# AMFS_PCB5.net
KiCad netlist of a schematic drawn in EAGLE
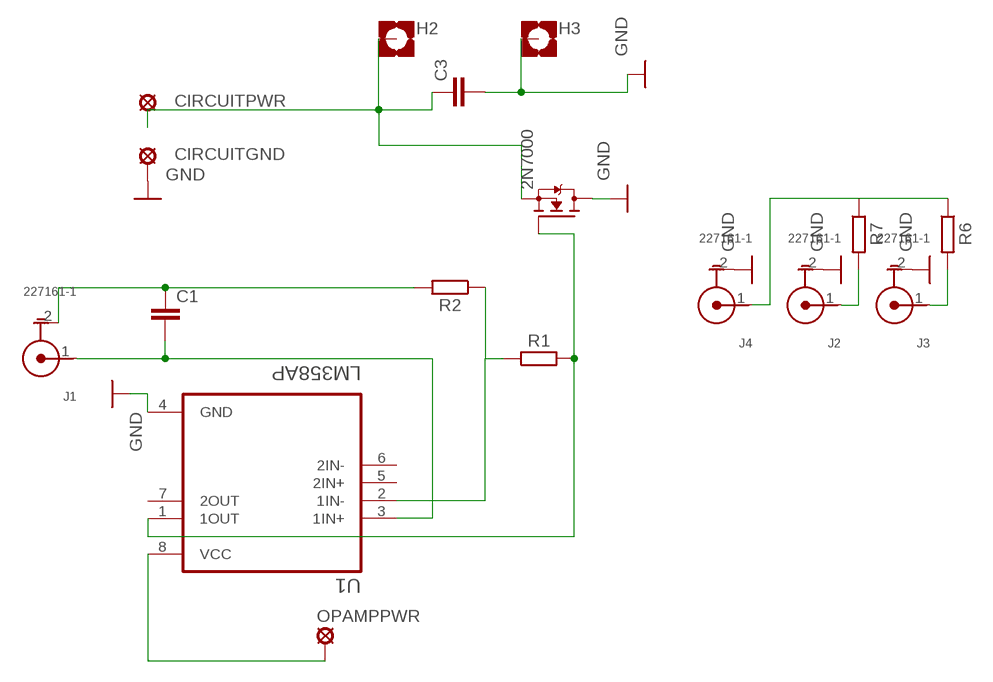
[diagram p0: schematic, sheet 1]

(export (version "E")
  (design (tool "Eeschema 10.0.6"))
  (components
    (comp (ref "C1")
      (value "C5/3.5")
      (footprint "eagle-import:C5B3.5")
      (libsource (lib "eagle-import") (part "C5/3.5"))
    )
    (comp (ref "C3")
      (value "C5/3.5")
      (footprint "eagle-import:C5B3.5")
      (libsource (lib "eagle-import") (part "C5/3.5"))
    )
    (comp (ref "CIRCUITGND")
      (value "MCS10B")
      (footprint "eagle-import:MCS10B")
      (libsource (lib "eagle-import") (part "MCS10B"))
    )
    (comp (ref "CIRCUITPWR")
      (value "MCS10B")
      (footprint "eagle-import:MCS10B")
      (libsource (lib "eagle-import") (part "MCS10B"))
    )
    (comp (ref "H2")
      (value "MOUNT-PAD-SQUARE2.8")
      (footprint "eagle-import:2,8-PAD-SQUARE")
      (libsource (lib "eagle-import") (part "MOUNT-PAD-SQUARE2.8"))
    )
    (comp (ref "H3")
      (value "MOUNT-PAD-SQUARE2.8")
      (footprint "eagle-import:2,8-PAD-SQUARE")
      (libsource (lib "eagle-import") (part "MOUNT-PAD-SQUARE2.8"))
    )
    (comp (ref "J1")
      (value "227161-1")
      (footprint "eagle-import:TE_227161-1")
      (fields (field (name "MF") "TE Connectivity"))
      (libsource (lib "eagle-import") (part "227161-1"))
    )
    (comp (ref "J2")
      (value "227161-1")
      (footprint "eagle-import:TE_227161-1")
      (fields (field (name "MF") "TE Connectivity"))
      (libsource (lib "eagle-import") (part "227161-1"))
    )
    (comp (ref "J3")
      (value "227161-1")
      (footprint "eagle-import:TE_227161-1")
      (fields (field (name "MF") "TE Connectivity"))
      (libsource (lib "eagle-import") (part "227161-1"))
    )
    (comp (ref "J4")
      (value "227161-1")
      (footprint "eagle-import:TE_227161-1")
      (fields (field (name "MF") "TE Connectivity"))
      (libsource (lib "eagle-import") (part "227161-1"))
    )
    (comp (ref "OPAMPPWR")
      (value "LSP10")
      (footprint "eagle-import:LSP10")
      (libsource (lib "eagle-import") (part "LSP10"))
    )
    (comp (ref "R1")
      (value "R_AXIAL-7.2MM-PITCH")
      (footprint "eagle-import:RESAD724W46L381D178B")
      (libsource (lib "eagle-import") (part "RAXIAL-7.2MM-PITCH_"))
    )
    (comp (ref "R2")
      (value "R_AXIAL-7.2MM-PITCH")
      (footprint "eagle-import:RESAD724W46L381D178B")
      (libsource (lib "eagle-import") (part "RAXIAL-7.2MM-PITCH_"))
    )
    (comp (ref "R6")
      (value "R_AXIAL-7.2MM-PITCH")
      (footprint "eagle-import:RESAD724W46L381D178B")
      (libsource (lib "eagle-import") (part "RAXIAL-7.2MM-PITCH_"))
    )
    (comp (ref "R7")
      (value "R_AXIAL-7.2MM-PITCH")
      (footprint "eagle-import:RESAD724W46L381D178B")
      (libsource (lib "eagle-import") (part "RAXIAL-7.2MM-PITCH_"))
    )
    (comp (ref "SHUNT")
      (value "2N7000")
      (footprint "eagle-import:TO92-")
      (fields (field (name "MF") "STMicroelectronics"))
      (libsource (lib "eagle-import") (part "2N7000"))
    )
    (comp (ref "U1")
      (value "LM358AP")
      (footprint "eagle-import:DIP794W45P254L959H508Q8")
      (fields (field (name "MF") "Texas Instruments"))
      (libsource (lib "eagle-import") (part "LM358AP"))
    )
  )
  (nets
    (net (code "1") (name "GND") (class "Default")
      (node (ref "C3") (pin "2") (pinfunction "2_2") (pintype "passive"))
      (node (ref "CIRCUITGND") (pin "MP") (pinfunction "MP_MP") (pintype "passive"))
      (node (ref "H3") (pin "B2,8") (pinfunction "MOUNT_B2,8") (pintype "passive"))
      (node (ref "J2") (pin "2") (pinfunction "G_2") (pintype "power_in"))
      (node (ref "J3") (pin "2") (pinfunction "G_2") (pintype "power_in"))
      (node (ref "J4") (pin "2") (pinfunction "G_2") (pintype "power_in"))
      (node (ref "SHUNT") (pin "1") (pinfunction "D_1") (pintype "passive"))
      (node (ref "U1") (pin "4") (pinfunction "GND_4") (pintype "power_in"))
    )
    (net (code "2") (name "Net-(H2-MOUNT)") (class "Default")
      (node (ref "C3") (pin "1") (pinfunction "1_1") (pintype "passive"))
      (node (ref "CIRCUITPWR") (pin "MP") (pinfunction "MP_MP") (pintype "passive"))
      (node (ref "H2") (pin "B2,8") (pinfunction "MOUNT_B2,8") (pintype "passive"))
      (node (ref "SHUNT") (pin "3") (pinfunction "S_3") (pintype "passive"))
    )
    (net (code "3") (name "Net-(J1-C)") (class "Default")
      (node (ref "C1") (pin "2") (pinfunction "2_2") (pintype "passive"))
      (node (ref "J1") (pin "1") (pinfunction "C_1") (pintype "passive"))
      (node (ref "U1") (pin "3") (pinfunction "1IN+_3") (pintype "input"))
    )
    (net (code "4") (name "Net-(J1-G)") (class "Default")
      (node (ref "C1") (pin "1") (pinfunction "1_1") (pintype "passive"))
      (node (ref "J1") (pin "2") (pinfunction "G_2") (pintype "power_in"))
      (node (ref "R2") (pin "2") (pinfunction "2_2") (pintype "passive"))
    )
    (net (code "5") (name "Net-(J2-C)") (class "Default")
      (node (ref "J2") (pin "1") (pinfunction "C_1") (pintype "passive"))
      (node (ref "R7") (pin "2") (pinfunction "2_2") (pintype "passive"))
    )
    (net (code "6") (name "Net-(J3-C)") (class "Default")
      (node (ref "J3") (pin "1") (pinfunction "C_1") (pintype "passive"))
      (node (ref "R6") (pin "2") (pinfunction "2_2") (pintype "passive"))
    )
    (net (code "7") (name "Net-(J4-C)") (class "Default")
      (node (ref "J4") (pin "1") (pinfunction "C_1") (pintype "passive"))
      (node (ref "R6") (pin "1") (pinfunction "1_1") (pintype "passive"))
      (node (ref "R7") (pin "1") (pinfunction "1_1") (pintype "passive"))
    )
    (net (code "8") (name "Net-(SHUNT-G)") (class "Default")
      (node (ref "R1") (pin "2") (pinfunction "2_2") (pintype "passive"))
      (node (ref "SHUNT") (pin "2") (pinfunction "G_2") (pintype "passive"))
      (node (ref "U1") (pin "1") (pinfunction "1OUT_1") (pintype "output"))
    )
    (net (code "9") (name "Net-(U1-1IN-)") (class "Default")
      (node (ref "R1") (pin "1") (pinfunction "1_1") (pintype "passive"))
      (node (ref "R2") (pin "1") (pinfunction "1_1") (pintype "passive"))
      (node (ref "U1") (pin "2") (pinfunction "1IN-_2") (pintype "input"))
    )
    (net (code "10") (name "Net-(U1-VCC)") (class "Default")
      (node (ref "OPAMPPWR") (pin "MP") (pinfunction "MP_MP") (pintype "passive"))
      (node (ref "U1") (pin "8") (pinfunction "VCC_8") (pintype "power_in"))
    )
    (net (code "11") (name "unconnected-(U1-2IN+-Pad5)") (class "Default")
      (node (ref "U1") (pin "5") (pinfunction "2IN+_5") (pintype "input"))
    )
    (net (code "12") (name "unconnected-(U1-2IN--Pad6)") (class "Default")
      (node (ref "U1") (pin "6") (pinfunction "2IN-_6") (pintype "input"))
    )
    (net (code "13") (name "unconnected-(U1-2OUT-Pad7)") (class "Default")
      (node (ref "U1") (pin "7") (pinfunction "2OUT_7") (pintype "output"))
    )
  )
)
